# BI7.net
KiCad netlist of a schematic drawn in Altium Designer
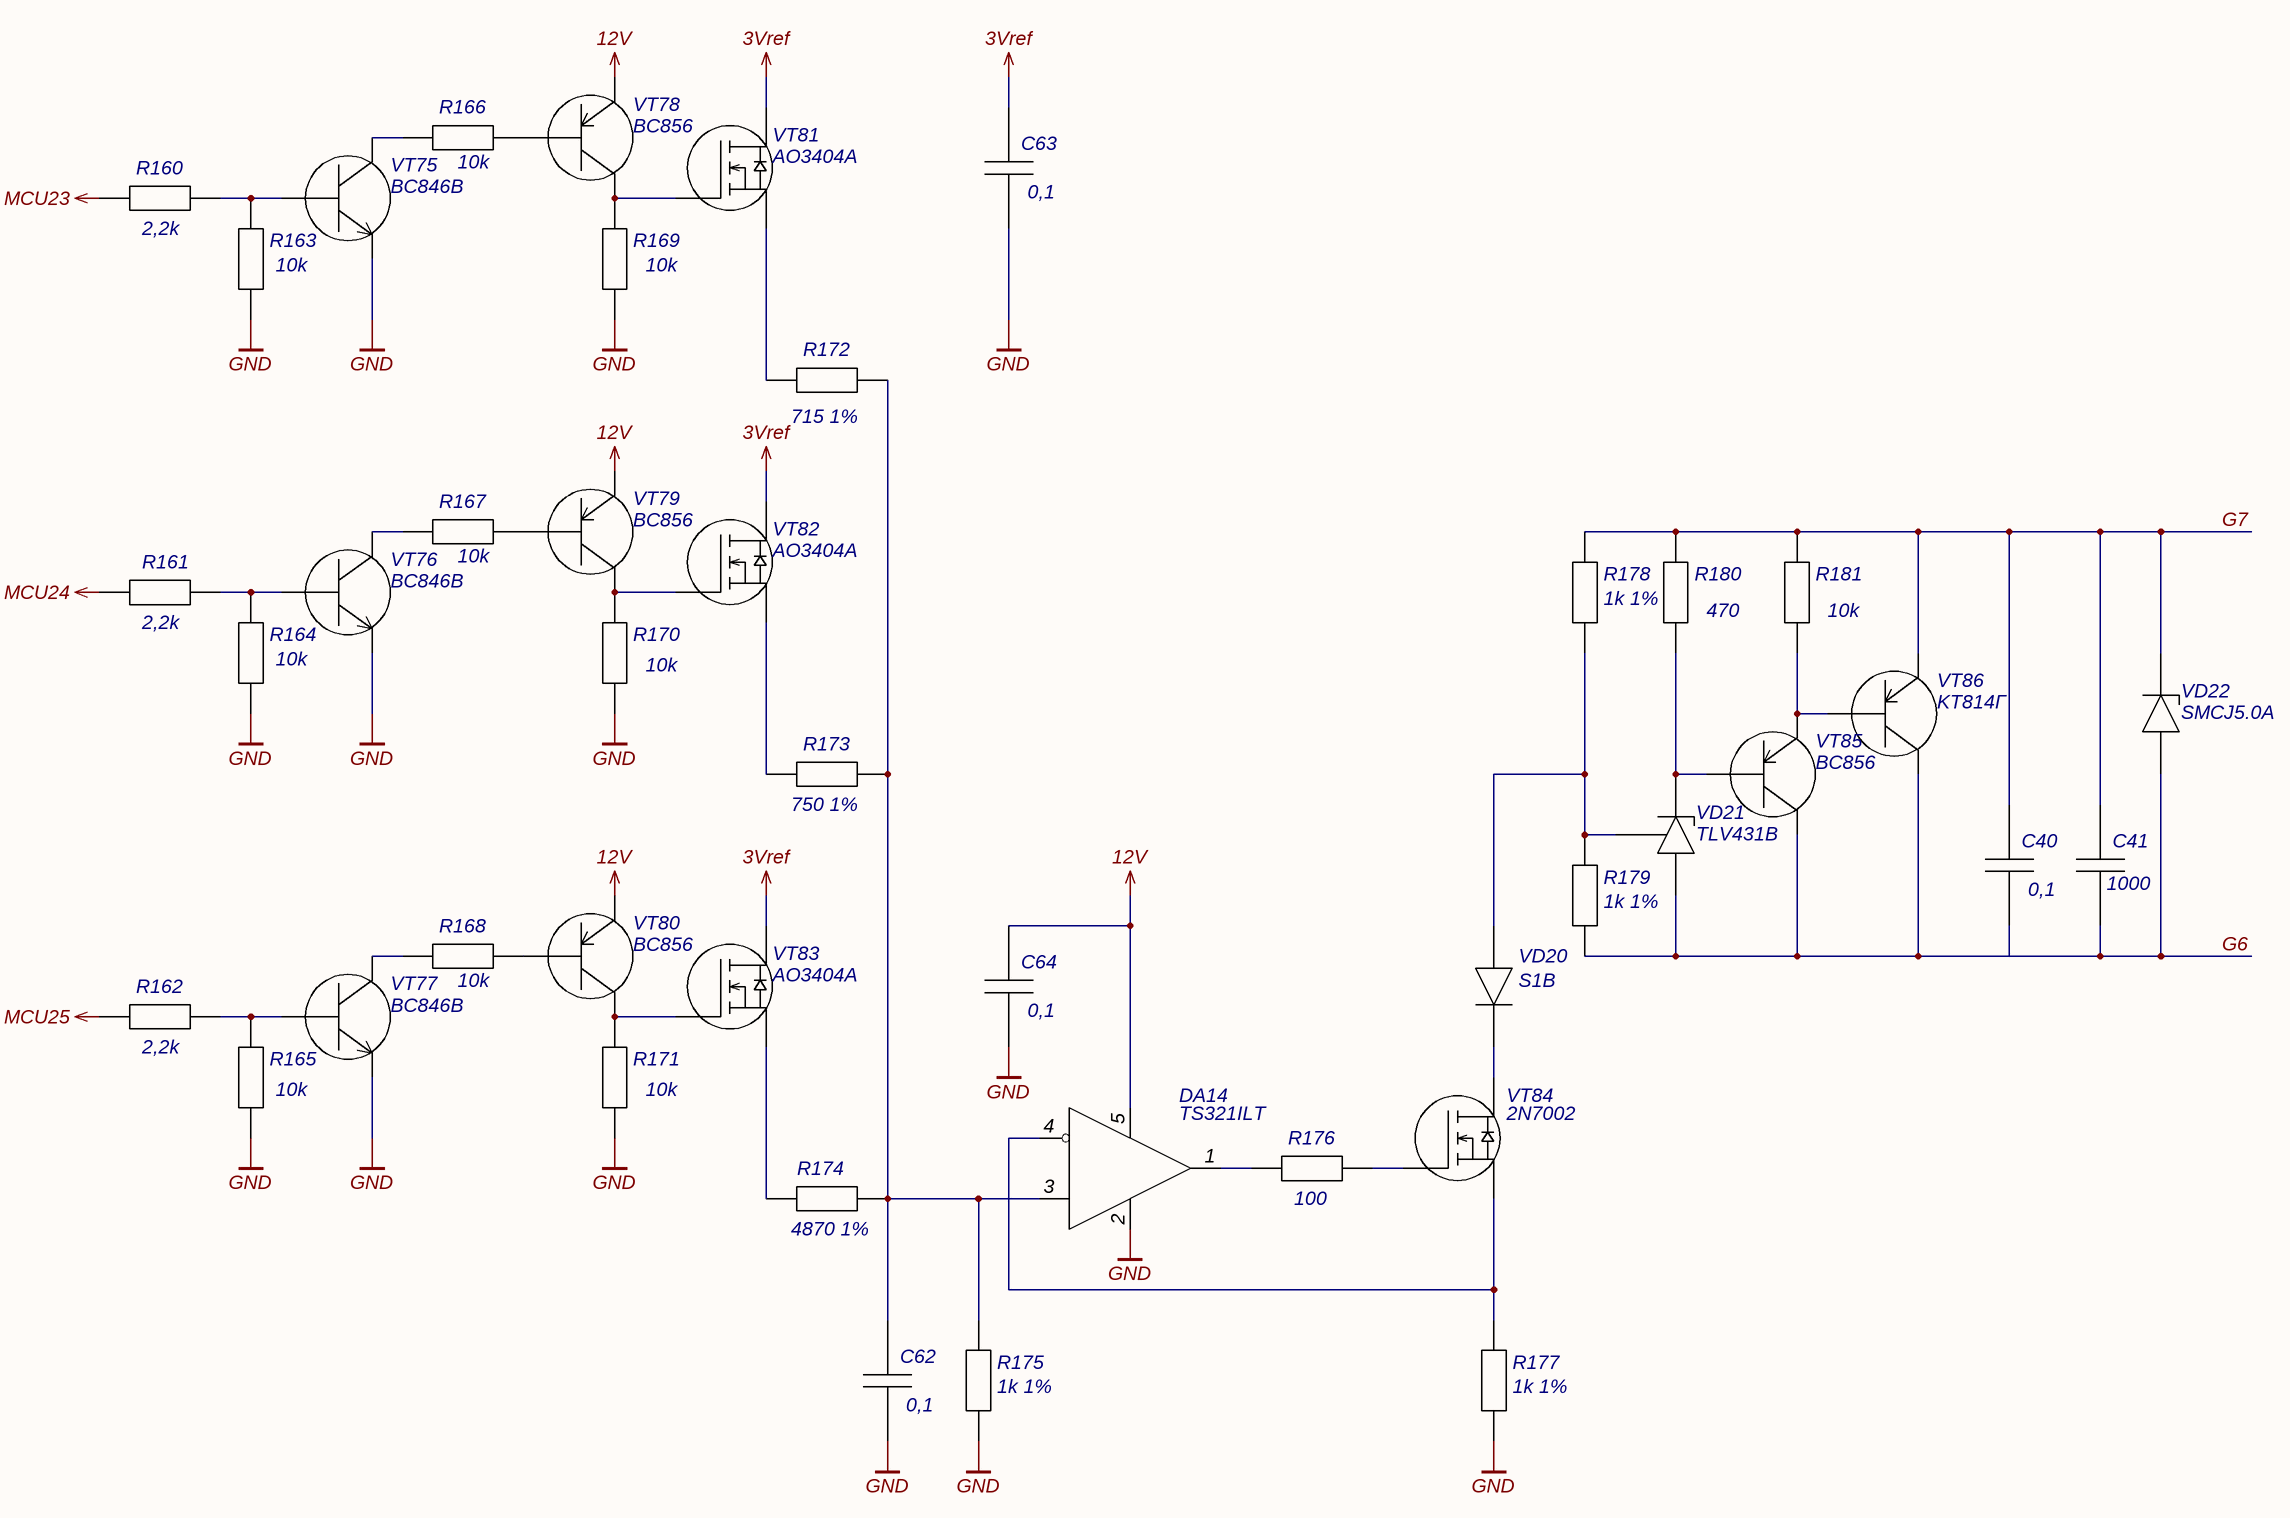
[diagram p0: BI7.SchDoc]

(export (version "E")
  (design (tool "Eeschema 10.0.6"))
  (components
    (comp (ref "C40")
      (value "0,1")
      (footprint "C0603")
      (description "Чип-конденсатор")
      (libsource (lib "Passive") (part "Chip Capasitor"))
    )
    (comp (ref "C41")
      (value "1000")
      (footprint "C0603")
      (description "Чип-конденсатор")
      (libsource (lib "Passive") (part "Chip Capasitor"))
    )
    (comp (ref "C62")
      (value "0,1")
      (footprint "C0603")
      (description "Чип-конденсатор")
      (libsource (lib "Passive") (part "Chip Capasitor"))
    )
    (comp (ref "C63")
      (value "0,1")
      (footprint "C0603")
      (description "Чип-конденсатор")
      (libsource (lib "Passive") (part "Chip Capasitor"))
    )
    (comp (ref "C64")
      (value "0,1")
      (footprint "C0603")
      (description "Чип-конденсатор")
      (libsource (lib "Passive") (part "Chip Capasitor"))
    )
    (comp (ref "DA14")
      (value "TS321ILT")
      (footprint "SOT-23-5")
      (description "1х Операционный усилитель")
      (libsource (lib "Schlib") (part "TS321ILT"))
    )
    (comp (ref "R160")
      (value "2,2k")
      (footprint "R0603")
      (description "Чип-резистор")
      (libsource (lib "") (part "Chip Resistor_1"))
    )
    (comp (ref "R161")
      (value "2,2k")
      (footprint "R0603")
      (description "Чип-резистор")
      (libsource (lib "") (part "Chip Resistor_1"))
    )
    (comp (ref "R162")
      (value "2,2k")
      (footprint "R0603")
      (description "Чип-резистор")
      (libsource (lib "") (part "Chip Resistor_1"))
    )
    (comp (ref "R163")
      (value "10k")
      (footprint "R0603")
      (description "Чип-резистор")
      (libsource (lib "Passive") (part "Chip Resistor"))
    )
    (comp (ref "R164")
      (value "10k")
      (footprint "R0603")
      (description "Чип-резистор")
      (libsource (lib "Passive") (part "Chip Resistor"))
    )
    (comp (ref "R165")
      (value "10k")
      (footprint "R0603")
      (description "Чип-резистор")
      (libsource (lib "Passive") (part "Chip Resistor"))
    )
    (comp (ref "R166")
      (value "10k")
      (footprint "R0603")
      (description "Чип-резистор")
      (libsource (lib "") (part "Chip Resistor_1"))
    )
    (comp (ref "R167")
      (value "10k")
      (footprint "R0603")
      (description "Чип-резистор")
      (libsource (lib "") (part "Chip Resistor_1"))
    )
    (comp (ref "R168")
      (value "10k")
      (footprint "R0603")
      (description "Чип-резистор")
      (libsource (lib "") (part "Chip Resistor_1"))
    )
    (comp (ref "R169")
      (value "10k")
      (footprint "R0603")
      (description "Чип-резистор")
      (libsource (lib "Passive") (part "Chip Resistor"))
    )
    (comp (ref "R170")
      (value "10k")
      (footprint "R0603")
      (description "Чип-резистор")
      (libsource (lib "Passive") (part "Chip Resistor"))
    )
    (comp (ref "R171")
      (value "10k")
      (footprint "R0603")
      (description "Чип-резистор")
      (libsource (lib "Passive") (part "Chip Resistor"))
    )
    (comp (ref "R172")
      (value "715 1%")
      (footprint "R0603")
      (description "Чип-резистор")
      (fields (field (name "PARTNUMBER") "RC0603FR-07715RL"))
      (libsource (lib "") (part "Chip Resistor_1"))
    )
    (comp (ref "R173")
      (value "750 1%")
      (footprint "R0603")
      (description "Чип-резистор")
      (fields (field (name "PARTNUMBER") "RC0603FR-07750RL"))
      (libsource (lib "") (part "Chip Resistor_1"))
    )
    (comp (ref "R174")
      (value "4870 1%")
      (footprint "R0603")
      (description "Чип-резистор")
      (fields (field (name "PARTNUMBER") "RC0603FR-074K87L"))
      (libsource (lib "") (part "Chip Resistor_1"))
    )
    (comp (ref "R175")
      (value "1k 1%")
      (footprint "R0603")
      (description "Чип-резистор")
      (fields (field (name "PARTNUMBER") "CRCW06031K00FKEAC"))
      (libsource (lib "Passive") (part "Chip Resistor"))
    )
    (comp (ref "R176")
      (value "100")
      (footprint "R0603")
      (description "Чип-резистор")
      (libsource (lib "") (part "Chip Resistor_1"))
    )
    (comp (ref "R177")
      (value "1k 1%")
      (footprint "R0603")
      (description "Чип-резистор")
      (fields (field (name "PARTNUMBER") "CRCW06031K00FKEAC"))
      (libsource (lib "Passive") (part "Chip Resistor"))
    )
    (comp (ref "R178")
      (value "1k 1%")
      (footprint "R0603")
      (description "Чип-резистор")
      (fields (field (name "PARTNUMBER") "CRCW06031K00FKEAC"))
      (libsource (lib "Passive") (part "Chip Resistor"))
    )
    (comp (ref "R179")
      (value "1k 1%")
      (footprint "R0603")
      (description "Чип-резистор")
      (fields (field (name "PARTNUMBER") "CRCW06031K00FKEAC"))
      (libsource (lib "Passive") (part "Chip Resistor"))
    )
    (comp (ref "R180")
      (value "470")
      (footprint "R0603")
      (description "Чип-резистор")
      (libsource (lib "Passive") (part "Chip Resistor"))
    )
    (comp (ref "R181")
      (value "10k")
      (footprint "R0603")
      (description "Чип-резистор")
      (libsource (lib "Passive") (part "Chip Resistor"))
    )
    (comp (ref "VD20")
      (value "S1B")
      (footprint "DO-214AC")
      (description "Диод выпрямительный, 100В")
      (fields (field (name "MANUFACTURER") "Diotec Semiconductor"))
      (libsource (lib "Schlib") (part "S1B"))
    )
    (comp (ref "VD21")
      (value "TLV431B")
      (footprint "SOT-23")
      (description "Стабилитрон регулируемый, 6В")
      (fields (field (name "MANUFACTURER") "Texas Instruments"))
      (libsource (lib "Schlib") (part "TLV431B"))
    )
    (comp (ref "VD22")
      (value "SMCJ5.0A")
      (footprint "DO-214AB")
      (description "Защитный диод, 5В")
      (fields (field (name "MANUFACTURER") "UTD Semiconductor Co.,Ltd"))
      (libsource (lib "Schlib") (part "SMCJ5.0A"))
    )
    (comp (ref "VT75")
      (value "BC846B")
      (footprint "SOT-23")
      (description "Транзистор биполярный NPN, 65В")
      (fields (field (name "MANUFACTURER") "Nexperia B.V."))
      (libsource (lib "Schlib") (part "BC846B"))
    )
    (comp (ref "VT76")
      (value "BC846B")
      (footprint "SOT-23")
      (description "Транзистор биполярный NPN, 65В")
      (fields (field (name "MANUFACTURER") "Nexperia B.V."))
      (libsource (lib "Schlib") (part "BC846B"))
    )
    (comp (ref "VT77")
      (value "BC846B")
      (footprint "SOT-23")
      (description "Транзистор биполярный NPN, 65В")
      (fields (field (name "MANUFACTURER") "Nexperia B.V."))
      (libsource (lib "Schlib") (part "BC846B"))
    )
    (comp (ref "VT78")
      (value "BC856")
      (footprint "SOT-23")
      (description "Транзистор биполярный PNP, 65В")
      (fields (field (name "MANUFACTURER") "Nexperia"))
      (libsource (lib "Schlib") (part "BC856"))
    )
    (comp (ref "VT79")
      (value "BC856")
      (footprint "SOT-23")
      (description "Транзистор биполярный PNP, 65В")
      (fields (field (name "MANUFACTURER") "Nexperia"))
      (libsource (lib "Schlib") (part "BC856"))
    )
    (comp (ref "VT80")
      (value "BC856")
      (footprint "SOT-23")
      (description "Транзистор биполярный PNP, 65В")
      (fields (field (name "MANUFACTURER") "Nexperia"))
      (libsource (lib "Schlib") (part "BC856"))
    )
    (comp (ref "VT81")
      (value "AO3404A")
      (footprint "SOT-23")
      (description "Транзистор MOSFET N-канал, 30В")
      (fields (field (name "MANUFACTURER") "UTD Semiconductor Co.,Ltd"))
      (libsource (lib "Schlib") (part "AO3404A"))
    )
    (comp (ref "VT82")
      (value "AO3404A")
      (footprint "SOT-23")
      (description "Транзистор MOSFET N-канал, 30В")
      (fields (field (name "MANUFACTURER") "UTD Semiconductor Co.,Ltd"))
      (libsource (lib "Schlib") (part "AO3404A"))
    )
    (comp (ref "VT83")
      (value "AO3404A")
      (footprint "SOT-23")
      (description "Транзистор MOSFET N-канал, 30В")
      (fields (field (name "MANUFACTURER") "UTD Semiconductor Co.,Ltd"))
      (libsource (lib "Schlib") (part "AO3404A"))
    )
    (comp (ref "VT84")
      (value "2N7002")
      (footprint "SOT-23")
      (description "Транзистор MOSFET N-канал, 60В")
      (fields (field (name "MANUFACTURER") "UTD Semiconductor Co."))
      (libsource (lib "Schlib") (part "2N7002"))
    )
    (comp (ref "VT85")
      (value "BC856")
      (footprint "SOT-23")
      (description "Транзистор биполярный PNP, 65В")
      (fields (field (name "MANUFACTURER") "Nexperia"))
      (libsource (lib "Schlib") (part "BC856"))
    )
    (comp (ref "VT86")
      (value "KT814Г")
      (footprint "TO-126")
      (description "Транзистор биполярный PNP, 100В")
      (fields (field (name "MANUFACTURER") "АО «ГРУППА КРЕМНИЙ ЭЛ»"))
      (libsource (lib "Schlib") (part "KT814Г"))
    )
  )
  (nets
    (net (code "1") (name "/G6") (class "Default")
      (node (ref "C40") (pin "1") (pinfunction "1_1") (pintype "passive"))
      (node (ref "C41") (pin "1") (pinfunction "1_1") (pintype "passive"))
      (node (ref "R179") (pin "1") (pinfunction "1_1") (pintype "passive"))
      (node (ref "VD21") (pin "1") (pinfunction "1_1") (pintype "passive"))
      (node (ref "VD22") (pin "1") (pinfunction "1_1") (pintype "passive"))
      (node (ref "VT85") (pin "2") (pinfunction "2_2") (pintype "passive"))
      (node (ref "VT86") (pin "2") (pinfunction "2_2") (pintype "passive"))
    )
    (net (code "2") (name "/G7") (class "Default")
      (node (ref "C40") (pin "2") (pinfunction "2_2") (pintype "passive"))
      (node (ref "C41") (pin "2") (pinfunction "2_2") (pintype "passive"))
      (node (ref "R178") (pin "2") (pinfunction "2_2") (pintype "passive"))
      (node (ref "R180") (pin "2") (pinfunction "2_2") (pintype "passive"))
      (node (ref "R181") (pin "2") (pinfunction "2_2") (pintype "passive"))
      (node (ref "VD22") (pin "2") (pinfunction "2_2") (pintype "passive"))
      (node (ref "VT86") (pin "1") (pinfunction "1_1") (pintype "passive"))
    )
    (net (code "3") (name "3Vref") (class "Default")
      (node (ref "C63") (pin "2") (pinfunction "2_2") (pintype "passive"))
      (node (ref "VT81") (pin "2") (pinfunction "D_2") (pintype "passive"))
      (node (ref "VT82") (pin "2") (pinfunction "D_2") (pintype "passive"))
      (node (ref "VT83") (pin "2") (pinfunction "D_2") (pintype "passive"))
    )
    (net (code "4") (name "12V") (class "Default")
      (node (ref "C64") (pin "2") (pinfunction "2_2") (pintype "passive"))
      (node (ref "DA14") (pin "5") (pinfunction "Vcc_5") (pintype "passive"))
      (node (ref "VT78") (pin "1") (pinfunction "1_1") (pintype "passive"))
      (node (ref "VT79") (pin "1") (pinfunction "1_1") (pintype "passive"))
      (node (ref "VT80") (pin "1") (pinfunction "1_1") (pintype "passive"))
    )
    (net (code "5") (name "GND") (class "Default")
      (node (ref "C62") (pin "1") (pinfunction "1_1") (pintype "passive"))
      (node (ref "C63") (pin "1") (pinfunction "1_1") (pintype "passive"))
      (node (ref "C64") (pin "1") (pinfunction "1_1") (pintype "passive"))
      (node (ref "DA14") (pin "2") (pinfunction "GND_2") (pintype "passive"))
      (node (ref "R163") (pin "1") (pinfunction "1_1") (pintype "passive"))
      (node (ref "R164") (pin "1") (pinfunction "1_1") (pintype "passive"))
      (node (ref "R165") (pin "1") (pinfunction "1_1") (pintype "passive"))
      (node (ref "R169") (pin "1") (pinfunction "1_1") (pintype "passive"))
      (node (ref "R170") (pin "1") (pinfunction "1_1") (pintype "passive"))
      (node (ref "R171") (pin "1") (pinfunction "1_1") (pintype "passive"))
      (node (ref "R175") (pin "1") (pinfunction "1_1") (pintype "passive"))
      (node (ref "R177") (pin "1") (pinfunction "1_1") (pintype "passive"))
      (node (ref "VT75") (pin "2") (pinfunction "E_2") (pintype "passive"))
      (node (ref "VT76") (pin "2") (pinfunction "E_2") (pintype "passive"))
      (node (ref "VT77") (pin "2") (pinfunction "E_2") (pintype "passive"))
    )
    (net (code "6") (name "MCU23") (class "Default")
      (node (ref "R160") (pin "1") (pinfunction "1_1") (pintype "passive"))
    )
    (net (code "7") (name "MCU24") (class "Default")
      (node (ref "R161") (pin "1") (pinfunction "1_1") (pintype "passive"))
    )
    (net (code "8") (name "MCU25") (class "Default")
      (node (ref "R162") (pin "1") (pinfunction "1_1") (pintype "passive"))
    )
    (net (code "9") (name "Net-(DA14-+)") (class "Default")
      (node (ref "C62") (pin "2") (pinfunction "2_2") (pintype "passive"))
      (node (ref "DA14") (pin "3") (pinfunction "+_3") (pintype "passive"))
      (node (ref "R172") (pin "2") (pinfunction "2_2") (pintype "passive"))
      (node (ref "R173") (pin "2") (pinfunction "2_2") (pintype "passive"))
      (node (ref "R174") (pin "2") (pinfunction "2_2") (pintype "passive"))
      (node (ref "R175") (pin "2") (pinfunction "2_2") (pintype "passive"))
    )
    (net (code "10") (name "Net-(DA14--)") (class "Default")
      (node (ref "DA14") (pin "4") (pinfunction "-_4") (pintype "passive"))
      (node (ref "R177") (pin "2") (pinfunction "2_2") (pintype "passive"))
      (node (ref "VT84") (pin "3") (pinfunction "S_3") (pintype "passive"))
    )
    (net (code "11") (name "Net-(DA14-OUT)") (class "Default")
      (node (ref "DA14") (pin "1") (pinfunction "OUT_1") (pintype "passive"))
      (node (ref "R176") (pin "1") (pinfunction "1_1") (pintype "passive"))
    )
    (net (code "12") (name "Net-(R166-Pad2)") (class "Default")
      (node (ref "R166") (pin "2") (pinfunction "2_2") (pintype "passive"))
      (node (ref "VT78") (pin "3") (pinfunction "3_3") (pintype "passive"))
    )
    (net (code "13") (name "Net-(R167-Pad2)") (class "Default")
      (node (ref "R167") (pin "2") (pinfunction "2_2") (pintype "passive"))
      (node (ref "VT79") (pin "3") (pinfunction "3_3") (pintype "passive"))
    )
    (net (code "14") (name "Net-(R168-Pad2)") (class "Default")
      (node (ref "R168") (pin "2") (pinfunction "2_2") (pintype "passive"))
      (node (ref "VT80") (pin "3") (pinfunction "3_3") (pintype "passive"))
    )
    (net (code "15") (name "Net-(R178-Pad1)") (class "Default")
      (node (ref "R178") (pin "1") (pinfunction "1_1") (pintype "passive"))
      (node (ref "R179") (pin "2") (pinfunction "2_2") (pintype "passive"))
      (node (ref "VD20") (pin "1") (pinfunction "1_1") (pintype "passive"))
      (node (ref "VD21") (pin "3") (pinfunction "3_3") (pintype "passive"))
    )
    (net (code "16") (name "Net-(R180-Pad1)") (class "Default")
      (node (ref "R180") (pin "1") (pinfunction "1_1") (pintype "passive"))
      (node (ref "VD21") (pin "2") (pinfunction "2_2") (pintype "passive"))
      (node (ref "VT85") (pin "3") (pinfunction "3_3") (pintype "passive"))
    )
    (net (code "17") (name "Net-(R181-Pad1)") (class "Default")
      (node (ref "R181") (pin "1") (pinfunction "1_1") (pintype "passive"))
      (node (ref "VT85") (pin "1") (pinfunction "1_1") (pintype "passive"))
      (node (ref "VT86") (pin "3") (pinfunction "3_3") (pintype "passive"))
    )
    (net (code "18") (name "Net-(VT75-B)") (class "Default")
      (node (ref "R160") (pin "2") (pinfunction "2_2") (pintype "passive"))
      (node (ref "R163") (pin "2") (pinfunction "2_2") (pintype "passive"))
      (node (ref "VT75") (pin "1") (pinfunction "B_1") (pintype "passive"))
    )
    (net (code "19") (name "Net-(VT75-C)") (class "Default")
      (node (ref "R166") (pin "1") (pinfunction "1_1") (pintype "passive"))
      (node (ref "VT75") (pin "3") (pinfunction "C_3") (pintype "passive"))
    )
    (net (code "20") (name "Net-(VT76-B)") (class "Default")
      (node (ref "R161") (pin "2") (pinfunction "2_2") (pintype "passive"))
      (node (ref "R164") (pin "2") (pinfunction "2_2") (pintype "passive"))
      (node (ref "VT76") (pin "1") (pinfunction "B_1") (pintype "passive"))
    )
    (net (code "21") (name "Net-(VT76-C)") (class "Default")
      (node (ref "R167") (pin "1") (pinfunction "1_1") (pintype "passive"))
      (node (ref "VT76") (pin "3") (pinfunction "C_3") (pintype "passive"))
    )
    (net (code "22") (name "Net-(VT77-B)") (class "Default")
      (node (ref "R162") (pin "2") (pinfunction "2_2") (pintype "passive"))
      (node (ref "R165") (pin "2") (pinfunction "2_2") (pintype "passive"))
      (node (ref "VT77") (pin "1") (pinfunction "B_1") (pintype "passive"))
    )
    (net (code "23") (name "Net-(VT77-C)") (class "Default")
      (node (ref "R168") (pin "1") (pinfunction "1_1") (pintype "passive"))
      (node (ref "VT77") (pin "3") (pinfunction "C_3") (pintype "passive"))
    )
    (net (code "24") (name "Net-(VT81-G)") (class "Default")
      (node (ref "R169") (pin "2") (pinfunction "2_2") (pintype "passive"))
      (node (ref "VT78") (pin "2") (pinfunction "2_2") (pintype "passive"))
      (node (ref "VT81") (pin "1") (pinfunction "G_1") (pintype "passive"))
    )
    (net (code "25") (name "Net-(VT81-S)") (class "Default")
      (node (ref "R172") (pin "1") (pinfunction "1_1") (pintype "passive"))
      (node (ref "VT81") (pin "3") (pinfunction "S_3") (pintype "passive"))
    )
    (net (code "26") (name "Net-(VT82-G)") (class "Default")
      (node (ref "R170") (pin "2") (pinfunction "2_2") (pintype "passive"))
      (node (ref "VT79") (pin "2") (pinfunction "2_2") (pintype "passive"))
      (node (ref "VT82") (pin "1") (pinfunction "G_1") (pintype "passive"))
    )
    (net (code "27") (name "Net-(VT82-S)") (class "Default")
      (node (ref "R173") (pin "1") (pinfunction "1_1") (pintype "passive"))
      (node (ref "VT82") (pin "3") (pinfunction "S_3") (pintype "passive"))
    )
    (net (code "28") (name "Net-(VT83-G)") (class "Default")
      (node (ref "R171") (pin "2") (pinfunction "2_2") (pintype "passive"))
      (node (ref "VT80") (pin "2") (pinfunction "2_2") (pintype "passive"))
      (node (ref "VT83") (pin "1") (pinfunction "G_1") (pintype "passive"))
    )
    (net (code "29") (name "Net-(VT83-S)") (class "Default")
      (node (ref "R174") (pin "1") (pinfunction "1_1") (pintype "passive"))
      (node (ref "VT83") (pin "3") (pinfunction "S_3") (pintype "passive"))
    )
    (net (code "30") (name "Net-(VT84-D)") (class "Default")
      (node (ref "VD20") (pin "2") (pinfunction "2_2") (pintype "passive"))
      (node (ref "VT84") (pin "2") (pinfunction "D_2") (pintype "passive"))
    )
    (net (code "31") (name "Net-(VT84-G)") (class "Default")
      (node (ref "R176") (pin "2") (pinfunction "2_2") (pintype "passive"))
      (node (ref "VT84") (pin "1") (pinfunction "G_1") (pintype "passive"))
    )
  )
)
